# fm-transmitter_v1_1.net
KiCad netlist of a schematic drawn in EAGLE
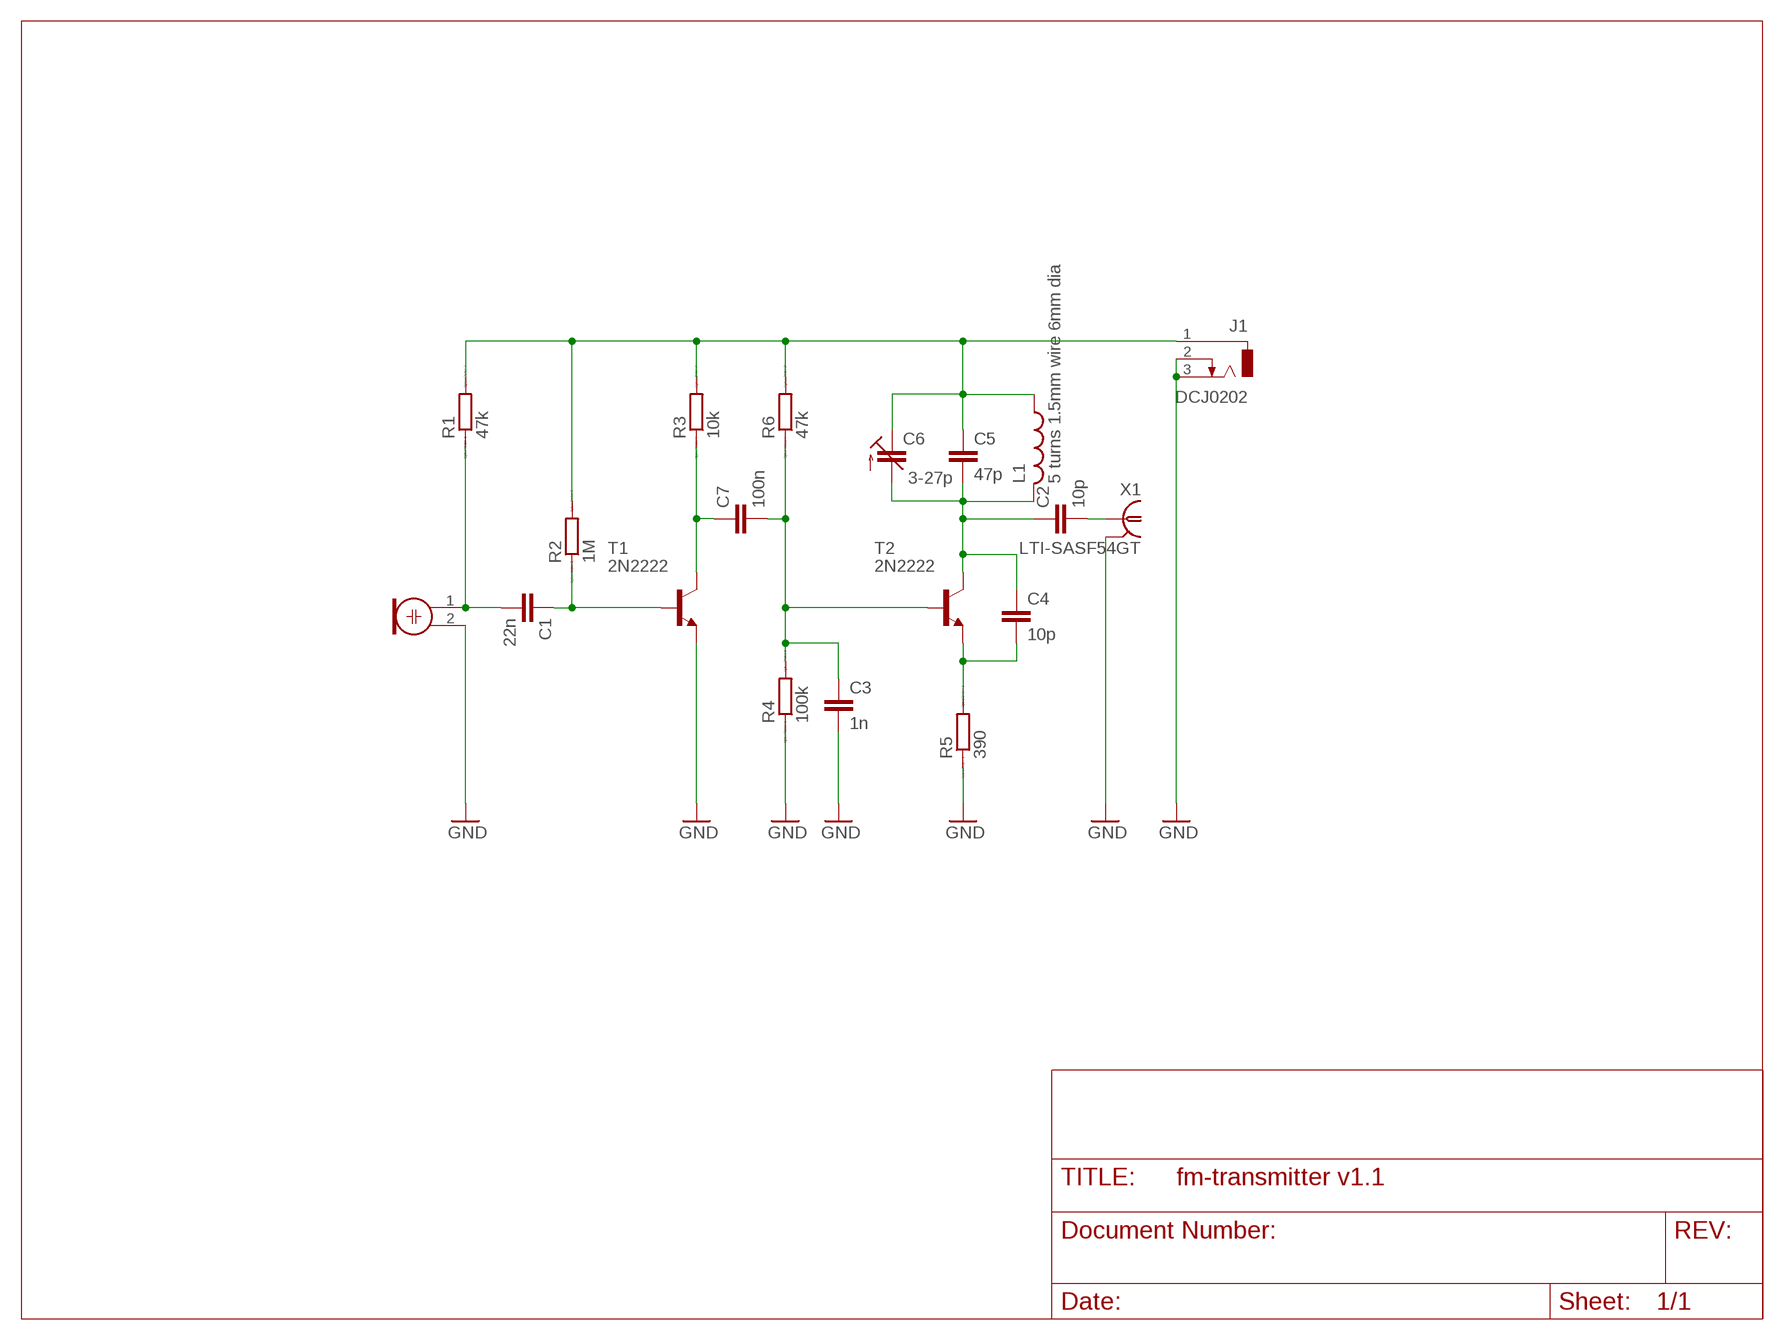
[diagram p0: schematic, sheet 1]

(export (version "E")
  (design (tool "Eeschema 10.0.6"))
  (components
    (comp (ref "C1")
      (value "22n")
      (footprint "eagle-import:C5B2.5")
      (libsource (lib "eagle-import") (part "C5/2.5"))
    )
    (comp (ref "C2")
      (value "10p")
      (footprint "eagle-import:C5B2.5")
      (libsource (lib "eagle-import") (part "C5/2.5"))
    )
    (comp (ref "C3")
      (value "1n")
      (footprint "eagle-import:C5B2.5")
      (libsource (lib "eagle-import") (part "C5/2.5"))
    )
    (comp (ref "C4")
      (value "10p")
      (footprint "eagle-import:C5B2.5")
      (libsource (lib "eagle-import") (part "C5/2.5"))
    )
    (comp (ref "C5")
      (value "47p")
      (footprint "eagle-import:C5B2.5")
      (libsource (lib "eagle-import") (part "C5/2.5"))
    )
    (comp (ref "C6")
      (value "3-27p")
      (footprint "eagle-import:CTRIM3050.504")
      (libsource (lib "eagle-import") (part "C-TRIMM3050.504"))
    )
    (comp (ref "C7")
      (value "100n")
      (footprint "eagle-import:C5B2.5")
      (libsource (lib "eagle-import") (part "C5/2.5"))
    )
    (comp (ref "J1")
      (value "DCJ0202")
      (footprint "eagle-import:DCJ0202")
      (libsource (lib "eagle-import") (part "DCJ0202"))
    )
    (comp (ref "L1")
      (value "5 turns 1.5mm wire 6mm dia")
      (footprint "eagle-import:0207_7")
      (libsource (lib "eagle-import") (part "L-US0207/7"))
    )
    (comp (ref "M1")
      (value "ELECTRET_MICROPHON-F6050AP")
      (footprint "eagle-import:F6050AP")
      (libsource (lib "eagle-import") (part "ELECTRET_MICROPHON-F6050AP"))
    )
    (comp (ref "R1")
      (value "47k")
      (footprint "eagle-import:0207_10")
      (libsource (lib "eagle-import") (part "R0207/10"))
    )
    (comp (ref "R2")
      (value "1M")
      (footprint "eagle-import:0207_10")
      (libsource (lib "eagle-import") (part "R0207/10"))
    )
    (comp (ref "R3")
      (value "10k")
      (footprint "eagle-import:0207_10")
      (libsource (lib "eagle-import") (part "R0207/10"))
    )
    (comp (ref "R4")
      (value "100k")
      (footprint "eagle-import:0207_10")
      (libsource (lib "eagle-import") (part "R0207/10"))
    )
    (comp (ref "R5")
      (value "390")
      (footprint "eagle-import:0207_10")
      (libsource (lib "eagle-import") (part "R0207/10"))
    )
    (comp (ref "R6")
      (value "47k")
      (footprint "eagle-import:0207_10")
      (libsource (lib "eagle-import") (part "R0207/10"))
    )
    (comp (ref "T1")
      (value "2N2222")
      (footprint "eagle-import:TO18")
      (libsource (lib "eagle-import") (part "2N2222"))
    )
    (comp (ref "T2")
      (value "2N2222")
      (footprint "eagle-import:TO18")
      (libsource (lib "eagle-import") (part "2N2222"))
    )
    (comp (ref "X1")
      (value "LTI-SASF54GT")
      (footprint "eagle-import:LTI-SASF54GT")
      (libsource (lib "eagle-import") (part "LTI-SASF54GT"))
    )
  )
  (nets
    (net (code "1") (name "GND") (class "Default")
      (node (ref "C3") (pin "2") (pinfunction "2_2") (pintype "passive"))
      (node (ref "J1") (pin "2") (pinfunction "2_2") (pintype "passive"))
      (node (ref "J1") (pin "3") (pinfunction "3_3") (pintype "passive"))
      (node (ref "M1") (pin "2") (pinfunction "2_2") (pintype "passive"))
      (node (ref "R4") (pin "1") (pinfunction "1_1") (pintype "passive"))
      (node (ref "R5") (pin "1") (pinfunction "1_1") (pintype "passive"))
      (node (ref "T1") (pin "1") (pinfunction "E_1") (pintype "passive"))
      (node (ref "X1") (pin "2") (pinfunction "2_2") (pintype "passive"))
      (node (ref "X1") (pin "3") (pinfunction "2_3") (pintype "passive"))
      (node (ref "X1") (pin "4") (pinfunction "2_4") (pintype "passive"))
      (node (ref "X1") (pin "5") (pinfunction "2_5") (pintype "passive"))
    )
    (net (code "2") (name "Net-(C1-Pad2)") (class "Default")
      (node (ref "C1") (pin "2") (pinfunction "2_2") (pintype "passive"))
      (node (ref "M1") (pin "1") (pinfunction "1_1") (pintype "passive"))
      (node (ref "R1") (pin "1") (pinfunction "1_1") (pintype "passive"))
    )
    (net (code "3") (name "Net-(C2-Pad2)") (class "Default")
      (node (ref "C2") (pin "2") (pinfunction "2_2") (pintype "passive"))
      (node (ref "X1") (pin "1") (pinfunction "1_1") (pintype "passive"))
    )
    (net (code "4") (name "Net-(C6-A)") (class "Default")
      (node (ref "C2") (pin "1") (pinfunction "1_1") (pintype "passive"))
      (node (ref "C4") (pin "1") (pinfunction "1_1") (pintype "passive"))
      (node (ref "C5") (pin "2") (pinfunction "2_2") (pintype "passive"))
      (node (ref "C6") (pin "2") (pinfunction "A_2") (pintype "passive"))
      (node (ref "L1") (pin "2") (pinfunction "2_2") (pintype "passive"))
      (node (ref "T2") (pin "3") (pinfunction "C_3") (pintype "passive"))
    )
    (net (code "5") (name "Net-(C6-E)") (class "Default")
      (node (ref "C5") (pin "1") (pinfunction "1_1") (pintype "passive"))
      (node (ref "C6") (pin "1") (pinfunction "E_1") (pintype "passive"))
      (node (ref "J1") (pin "1") (pinfunction "1_1") (pintype "passive"))
      (node (ref "L1") (pin "1") (pinfunction "1_1") (pintype "passive"))
      (node (ref "R1") (pin "2") (pinfunction "2_2") (pintype "passive"))
      (node (ref "R2") (pin "2") (pinfunction "2_2") (pintype "passive"))
      (node (ref "R3") (pin "2") (pinfunction "2_2") (pintype "passive"))
      (node (ref "R6") (pin "2") (pinfunction "2_2") (pintype "passive"))
    )
    (net (code "6") (name "Net-(T1-B)") (class "Default")
      (node (ref "C1") (pin "1") (pinfunction "1_1") (pintype "passive"))
      (node (ref "R2") (pin "1") (pinfunction "1_1") (pintype "passive"))
      (node (ref "T1") (pin "2") (pinfunction "B_2") (pintype "passive"))
    )
    (net (code "7") (name "Net-(T1-C)") (class "Default")
      (node (ref "C7") (pin "1") (pinfunction "1_1") (pintype "passive"))
      (node (ref "R3") (pin "1") (pinfunction "1_1") (pintype "passive"))
      (node (ref "T1") (pin "3") (pinfunction "C_3") (pintype "passive"))
    )
    (net (code "8") (name "Net-(T2-B)") (class "Default")
      (node (ref "C3") (pin "1") (pinfunction "1_1") (pintype "passive"))
      (node (ref "C7") (pin "2") (pinfunction "2_2") (pintype "passive"))
      (node (ref "R4") (pin "2") (pinfunction "2_2") (pintype "passive"))
      (node (ref "R6") (pin "1") (pinfunction "1_1") (pintype "passive"))
      (node (ref "T2") (pin "2") (pinfunction "B_2") (pintype "passive"))
    )
    (net (code "9") (name "Net-(T2-E)") (class "Default")
      (node (ref "C4") (pin "2") (pinfunction "2_2") (pintype "passive"))
      (node (ref "R5") (pin "2") (pinfunction "2_2") (pintype "passive"))
      (node (ref "T2") (pin "1") (pinfunction "E_1") (pintype "passive"))
    )
  )
)
